# FrontPanel_v2.net
KiCad netlist of a schematic drawn in EAGLE
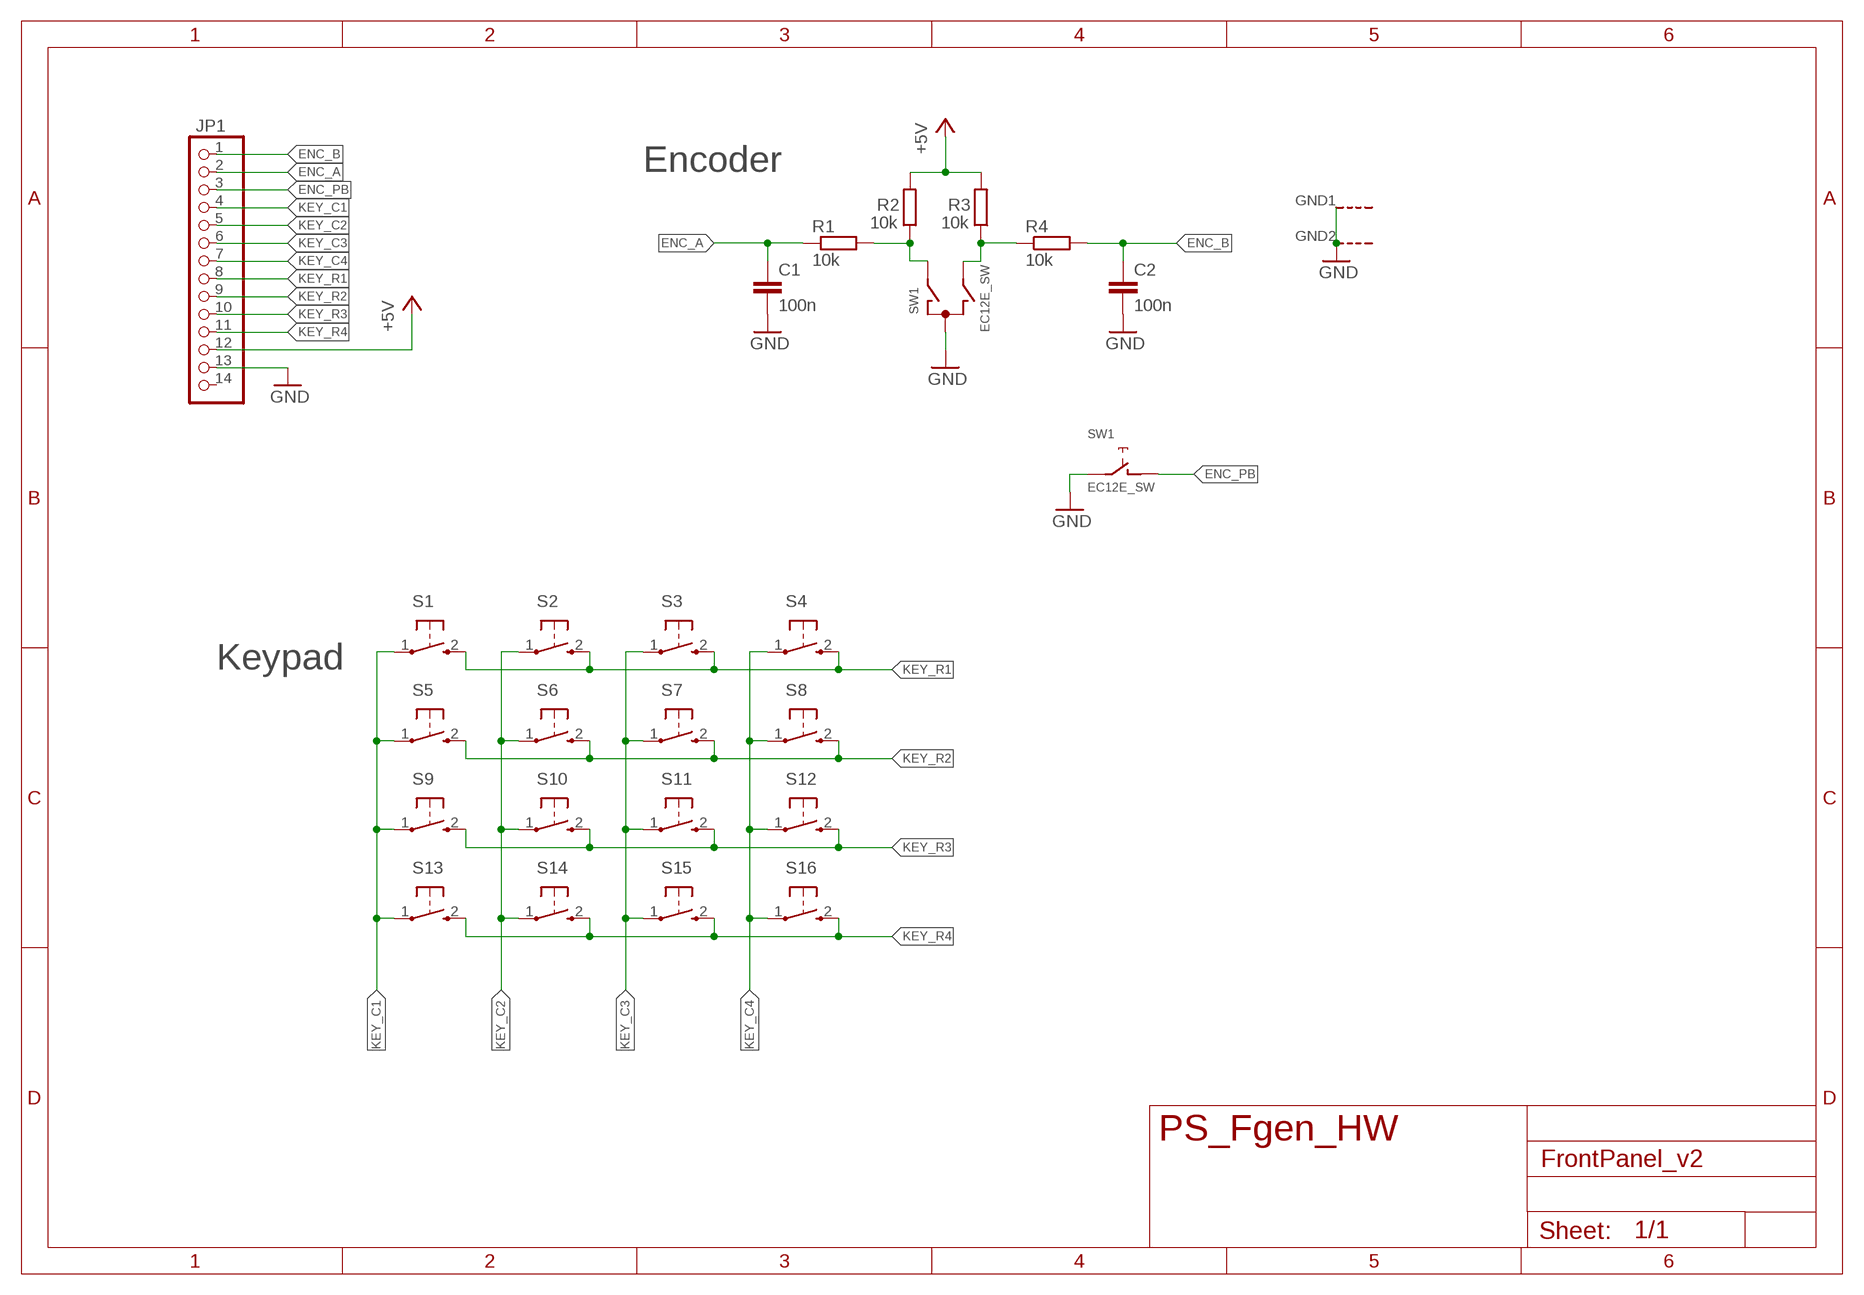
[diagram p0: schematic, sheet 1]

(export (version "E")
  (design (tool "Eeschema 10.0.6"))
  (components
    (comp (ref "C1")
      (value "100n")
      (footprint "eagle-import:C0805")
      (libsource (lib "eagle-import") (part "C-EUC0805"))
    )
    (comp (ref "C2")
      (value "100n")
      (footprint "eagle-import:C0805")
      (libsource (lib "eagle-import") (part "C-EUC0805"))
    )
    (comp (ref "JP1")
      (value "PINHD-1X14")
      (footprint "eagle-import:1X14")
      (libsource (lib "eagle-import") (part "PINHD-1X14"))
    )
    (comp (ref "R1")
      (value "10k")
      (footprint "eagle-import:R0805")
      (libsource (lib "eagle-import") (part "R-EU_R0805"))
    )
    (comp (ref "R2")
      (value "10k")
      (footprint "eagle-import:R0805")
      (libsource (lib "eagle-import") (part "R-EU_R0805"))
    )
    (comp (ref "R3")
      (value "10k")
      (footprint "eagle-import:R0805")
      (libsource (lib "eagle-import") (part "R-EU_R0805"))
    )
    (comp (ref "R4")
      (value "10k")
      (footprint "eagle-import:R0805")
      (libsource (lib "eagle-import") (part "R-EU_R0805"))
    )
    (comp (ref "S1")
      (value "KURZHUBTASTER")
      (footprint "eagle-import:B3F-10XX")
      (libsource (lib "eagle-import") (part "KURZHUBTASTER"))
    )
    (comp (ref "S2")
      (value "KURZHUBTASTER")
      (footprint "eagle-import:B3F-10XX")
      (libsource (lib "eagle-import") (part "KURZHUBTASTER"))
    )
    (comp (ref "S3")
      (value "KURZHUBTASTER")
      (footprint "eagle-import:B3F-10XX")
      (libsource (lib "eagle-import") (part "KURZHUBTASTER"))
    )
    (comp (ref "S4")
      (value "KURZHUBTASTER")
      (footprint "eagle-import:B3F-10XX")
      (libsource (lib "eagle-import") (part "KURZHUBTASTER"))
    )
    (comp (ref "S5")
      (value "KURZHUBTASTER")
      (footprint "eagle-import:B3F-10XX")
      (libsource (lib "eagle-import") (part "KURZHUBTASTER"))
    )
    (comp (ref "S6")
      (value "KURZHUBTASTER")
      (footprint "eagle-import:B3F-10XX")
      (libsource (lib "eagle-import") (part "KURZHUBTASTER"))
    )
    (comp (ref "S7")
      (value "KURZHUBTASTER")
      (footprint "eagle-import:B3F-10XX")
      (libsource (lib "eagle-import") (part "KURZHUBTASTER"))
    )
    (comp (ref "S8")
      (value "KURZHUBTASTER")
      (footprint "eagle-import:B3F-10XX")
      (libsource (lib "eagle-import") (part "KURZHUBTASTER"))
    )
    (comp (ref "S9")
      (value "KURZHUBTASTER")
      (footprint "eagle-import:B3F-10XX")
      (libsource (lib "eagle-import") (part "KURZHUBTASTER"))
    )
    (comp (ref "S10")
      (value "KURZHUBTASTER")
      (footprint "eagle-import:B3F-10XX")
      (libsource (lib "eagle-import") (part "KURZHUBTASTER"))
    )
    (comp (ref "S11")
      (value "KURZHUBTASTER")
      (footprint "eagle-import:B3F-10XX")
      (libsource (lib "eagle-import") (part "KURZHUBTASTER"))
    )
    (comp (ref "S12")
      (value "KURZHUBTASTER")
      (footprint "eagle-import:B3F-10XX")
      (libsource (lib "eagle-import") (part "KURZHUBTASTER"))
    )
    (comp (ref "S13")
      (value "KURZHUBTASTER")
      (footprint "eagle-import:B3F-10XX")
      (libsource (lib "eagle-import") (part "KURZHUBTASTER"))
    )
    (comp (ref "S14")
      (value "KURZHUBTASTER")
      (footprint "eagle-import:B3F-10XX")
      (libsource (lib "eagle-import") (part "KURZHUBTASTER"))
    )
    (comp (ref "S15")
      (value "KURZHUBTASTER")
      (footprint "eagle-import:B3F-10XX")
      (libsource (lib "eagle-import") (part "KURZHUBTASTER"))
    )
    (comp (ref "S16")
      (value "KURZHUBTASTER")
      (footprint "eagle-import:B3F-10XX")
      (libsource (lib "eagle-import") (part "KURZHUBTASTER"))
    )
    (comp (ref "SW1")
      (value "EC12E_SW")
      (footprint "eagle-import:ALPS_EC12E_SW")
      (fields (field (name "MPN") "EC12E2424407"))
      (libsource (lib "eagle-import") (part "EC12E_SW"))
    )
  )
  (nets
    (net (code "1") (name "+5V") (class "Default")
      (node (ref "JP1") (pin "12") (pinfunction "12_12") (pintype "passive"))
      (node (ref "R2") (pin "2") (pinfunction "2_2") (pintype "passive"))
      (node (ref "R3") (pin "2") (pinfunction "2_2") (pintype "passive"))
    )
    (net (code "2") (name "ENC_A") (class "Default")
      (node (ref "C1") (pin "1") (pinfunction "1_1") (pintype "passive"))
      (node (ref "JP1") (pin "2") (pinfunction "2_2") (pintype "passive"))
      (node (ref "R1") (pin "1") (pinfunction "1_1") (pintype "passive"))
    )
    (net (code "3") (name "ENC_B") (class "Default")
      (node (ref "C2") (pin "1") (pinfunction "1_1") (pintype "passive"))
      (node (ref "JP1") (pin "1") (pinfunction "1_1") (pintype "passive"))
      (node (ref "R4") (pin "2") (pinfunction "2_2") (pintype "passive"))
    )
    (net (code "4") (name "ENC_PB") (class "Default")
      (node (ref "JP1") (pin "3") (pinfunction "3_3") (pintype "passive"))
      (node (ref "SW1") (pin "D") (pinfunction "1_D") (pintype "passive"))
    )
    (net (code "5") (name "GND") (class "Default")
      (node (ref "C1") (pin "2") (pinfunction "2_2") (pintype "passive"))
      (node (ref "C2") (pin "2") (pinfunction "2_2") (pintype "passive"))
      (node (ref "JP1") (pin "13") (pinfunction "13_13") (pintype "passive"))
      (node (ref "SW1") (pin "C") (pinfunction "C_C") (pintype "passive"))
      (node (ref "SW1") (pin "E") (pinfunction "2_E") (pintype "passive"))
      (node (ref "SW1") (pin "GND1") (pinfunction "G_GND1") (pintype "passive"))
      (node (ref "SW1") (pin "GND2") (pinfunction "G_GND2") (pintype "passive"))
    )
    (net (code "6") (name "KEY_C1") (class "Default")
      (node (ref "JP1") (pin "4") (pinfunction "4_4") (pintype "passive"))
      (node (ref "S1") (pin "1") (pinfunction "P_1") (pintype "passive"))
      (node (ref "S13") (pin "1") (pinfunction "P_1") (pintype "passive"))
      (node (ref "S5") (pin "1") (pinfunction "P_1") (pintype "passive"))
      (node (ref "S9") (pin "1") (pinfunction "P_1") (pintype "passive"))
    )
    (net (code "7") (name "KEY_C2") (class "Default")
      (node (ref "JP1") (pin "5") (pinfunction "5_5") (pintype "passive"))
      (node (ref "S10") (pin "1") (pinfunction "P_1") (pintype "passive"))
      (node (ref "S14") (pin "1") (pinfunction "P_1") (pintype "passive"))
      (node (ref "S2") (pin "1") (pinfunction "P_1") (pintype "passive"))
      (node (ref "S6") (pin "1") (pinfunction "P_1") (pintype "passive"))
    )
    (net (code "8") (name "KEY_C3") (class "Default")
      (node (ref "JP1") (pin "6") (pinfunction "6_6") (pintype "passive"))
      (node (ref "S11") (pin "1") (pinfunction "P_1") (pintype "passive"))
      (node (ref "S15") (pin "1") (pinfunction "P_1") (pintype "passive"))
      (node (ref "S3") (pin "1") (pinfunction "P_1") (pintype "passive"))
      (node (ref "S7") (pin "1") (pinfunction "P_1") (pintype "passive"))
    )
    (net (code "9") (name "KEY_C4") (class "Default")
      (node (ref "JP1") (pin "7") (pinfunction "7_7") (pintype "passive"))
      (node (ref "S12") (pin "1") (pinfunction "P_1") (pintype "passive"))
      (node (ref "S16") (pin "1") (pinfunction "P_1") (pintype "passive"))
      (node (ref "S4") (pin "1") (pinfunction "P_1") (pintype "passive"))
      (node (ref "S8") (pin "1") (pinfunction "P_1") (pintype "passive"))
    )
    (net (code "10") (name "KEY_R1") (class "Default")
      (node (ref "JP1") (pin "8") (pinfunction "8_8") (pintype "passive"))
      (node (ref "S1") (pin "2") (pinfunction "S_2") (pintype "passive"))
      (node (ref "S2") (pin "2") (pinfunction "S_2") (pintype "passive"))
      (node (ref "S3") (pin "2") (pinfunction "S_2") (pintype "passive"))
      (node (ref "S4") (pin "2") (pinfunction "S_2") (pintype "passive"))
    )
    (net (code "11") (name "KEY_R2") (class "Default")
      (node (ref "JP1") (pin "9") (pinfunction "9_9") (pintype "passive"))
      (node (ref "S5") (pin "2") (pinfunction "S_2") (pintype "passive"))
      (node (ref "S6") (pin "2") (pinfunction "S_2") (pintype "passive"))
      (node (ref "S7") (pin "2") (pinfunction "S_2") (pintype "passive"))
      (node (ref "S8") (pin "2") (pinfunction "S_2") (pintype "passive"))
    )
    (net (code "12") (name "KEY_R3") (class "Default")
      (node (ref "JP1") (pin "10") (pinfunction "10_10") (pintype "passive"))
      (node (ref "S10") (pin "2") (pinfunction "S_2") (pintype "passive"))
      (node (ref "S11") (pin "2") (pinfunction "S_2") (pintype "passive"))
      (node (ref "S12") (pin "2") (pinfunction "S_2") (pintype "passive"))
      (node (ref "S9") (pin "2") (pinfunction "S_2") (pintype "passive"))
    )
    (net (code "13") (name "KEY_R4") (class "Default")
      (node (ref "JP1") (pin "11") (pinfunction "11_11") (pintype "passive"))
      (node (ref "S13") (pin "2") (pinfunction "S_2") (pintype "passive"))
      (node (ref "S14") (pin "2") (pinfunction "S_2") (pintype "passive"))
      (node (ref "S15") (pin "2") (pinfunction "S_2") (pintype "passive"))
      (node (ref "S16") (pin "2") (pinfunction "S_2") (pintype "passive"))
    )
    (net (code "14") (name "Net-(R1-Pad2)") (class "Default")
      (node (ref "R1") (pin "2") (pinfunction "2_2") (pintype "passive"))
      (node (ref "R2") (pin "1") (pinfunction "1_1") (pintype "passive"))
      (node (ref "SW1") (pin "A") (pinfunction "A_A") (pintype "passive"))
    )
    (net (code "15") (name "Net-(R3-Pad1)") (class "Default")
      (node (ref "R3") (pin "1") (pinfunction "1_1") (pintype "passive"))
      (node (ref "R4") (pin "1") (pinfunction "1_1") (pintype "passive"))
      (node (ref "SW1") (pin "B") (pinfunction "B_B") (pintype "passive"))
    )
    (net (code "16") (name "unconnected-(JP1-Pad14)") (class "Default")
      (node (ref "JP1") (pin "14") (pinfunction "14_14") (pintype "passive"))
    )
  )
)
